# Sheet1.net
KiCad netlist of a schematic drawn in Altium Designer
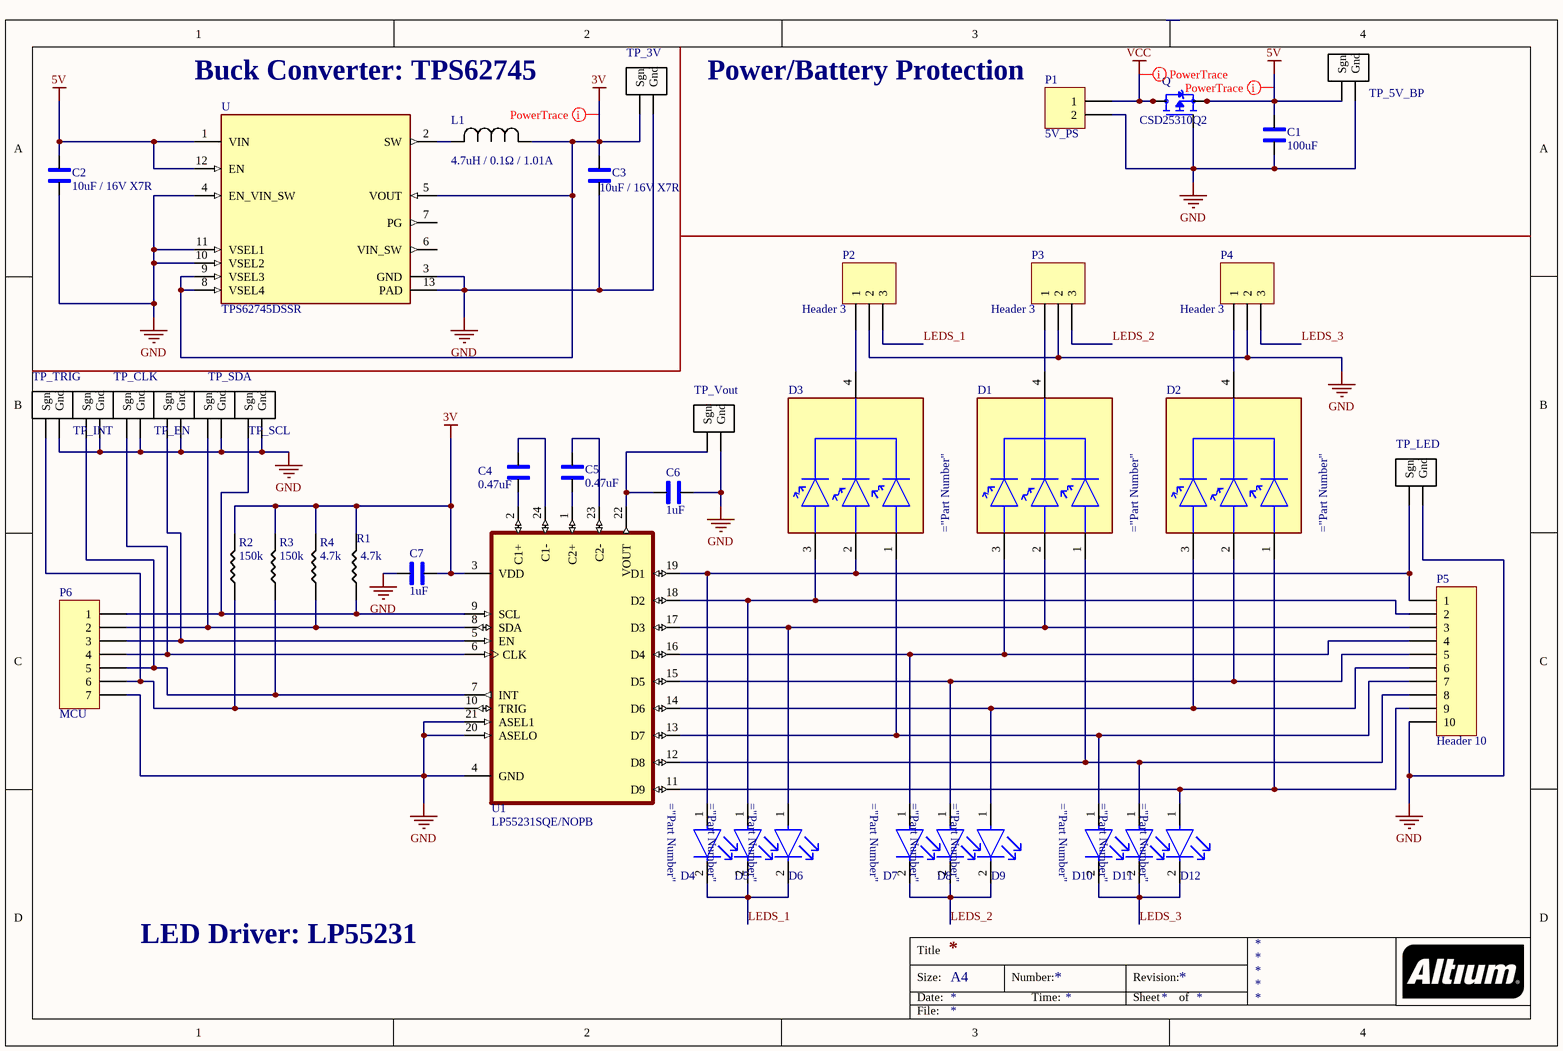
[diagram p0: Sheet1.SchDoc]

(export (version "E")
  (design (tool "Eeschema 10.0.6"))
  (components
    (comp (ref "C1")
      (value "100uF")
      (footprint "1206_Passive")
      (description "100µF X5R 1206 (3216 Metric)")
      (fields (field (name "DIGIKEY PART") "399-8150-1-ND") (field (name "MFR PART #") "CL31B105KBHNNNE"))
      (libsource (lib "ECEN5730Lib_2020_09_AR") (part "C_1uF_1206"))
    )
    (comp (ref "C2")
      (value "10uF / 16V X7R")
      (footprint "1206_Passive")
      (description "10µF ±20% 16V Ceramic Capacitor X7R 1206 (3216 Metric)")
      (fields (field (name "DIGIKEY PART") "399-8150-1-ND") (field (name "MFR PART #") "CL31B105KBHNNNE"))
      (libsource (lib "ECEN5730Lib_2020_09_AR") (part "C_1uF_1206"))
    )
    (comp (ref "C3")
      (value "10uF / 16V X7R")
      (footprint "1206_Passive")
      (description "10µF ±20% 16V Ceramic Capacitor X7R 1206 (3216 Metric)")
      (fields (field (name "DIGIKEY PART") "399-8150-1-ND") (field (name "MFR PART #") "CL31B105KBHNNNE"))
      (libsource (lib "ECEN5730Lib_2020_09_AR") (part "C_1uF_1206"))
    )
    (comp (ref "C4")
      (value "0.47uF")
      (footprint "1206_Passive")
      (description "0.47µF ±20% 16V Ceramic Capacitor X7R 1206 (3216 Metric)")
      (fields (field (name "DIGIKEY PART") "399-8150-1-ND") (field (name "MFR PART #") "CL31B105KBHNNNE"))
      (libsource (lib "ECEN5730Lib_2020_09_AR") (part "C_1uF_1206"))
    )
    (comp (ref "C5")
      (value "0.47uF")
      (footprint "1206_Passive")
      (description "0.47µF ±20% 16V Ceramic Capacitor X7R 1206 (3216 Metric)")
      (fields (field (name "DIGIKEY PART") "399-8150-1-ND") (field (name "MFR PART #") "CL31B105KBHNNNE"))
      (libsource (lib "ECEN5730Lib_2020_09_AR") (part "C_1uF_1206"))
    )
    (comp (ref "C6")
      (value "1uF")
      (footprint "1206_Passive")
      (description "1µF ±20% 16V Ceramic Capacitor X7R 1206 (3216 Metric)")
      (fields (field (name "DIGIKEY PART") "399-8150-1-ND") (field (name "MFR PART #") "CL31B105KBHNNNE"))
      (libsource (lib "ECEN5730Lib_2020_09_AR") (part "C_1uF_1206"))
    )
    (comp (ref "C7")
      (value "1uF")
      (footprint "1206_Passive")
      (description "1µF ±20% 16V Ceramic Capacitor X7R 1206 (3216 Metric)")
      (fields (field (name "DIGIKEY PART") "399-8150-1-ND") (field (name "MFR PART #") "CL31B105KBHNNNE"))
      (libsource (lib "ECEN5730Lib_2020_09_AR") (part "C_1uF_1206"))
    )
    (comp (ref "D1")
      (value "XZM2CRKM2DGFBB45SCCB")
      (footprint "SunLED_XZM2CRKM2DGFBB45SCCB_0")
      (libsource (lib "Schlib1") (part "XZM2CRKM2DGFBB45SCCB"))
    )
    (comp (ref "D2")
      (value "XZM2CRKM2DGFBB45SCCB")
      (footprint "SunLED_XZM2CRKM2DGFBB45SCCB_0")
      (libsource (lib "Schlib1") (part "XZM2CRKM2DGFBB45SCCB"))
    )
    (comp (ref "D3")
      (value "XZM2CRKM2DGFBB45SCCB")
      (footprint "SunLED_XZM2CRKM2DGFBB45SCCB_0")
      (libsource (lib "Schlib1") (part "XZM2CRKM2DGFBB45SCCB"))
    )
    (comp (ref "D4")
      (value "CLM3C-WKW-CWBYA453")
      (footprint "Cree_CLM3C-WKW_MFG")
      (libsource (lib "Schlib1") (part "CLM3C-WKW-CWBYA453"))
    )
    (comp (ref "D5")
      (value "CLM3C-WKW-CWBYA453")
      (footprint "Cree_CLM3C-WKW_MFG")
      (libsource (lib "Schlib1") (part "CLM3C-WKW-CWBYA453"))
    )
    (comp (ref "D6")
      (value "CLM3C-WKW-CWBYA453")
      (footprint "Cree_CLM3C-WKW_MFG")
      (libsource (lib "Schlib1") (part "CLM3C-WKW-CWBYA453"))
    )
    (comp (ref "D7")
      (value "CLM3C-WKW-CWBYA453")
      (footprint "Cree_CLM3C-WKW_MFG")
      (libsource (lib "Schlib1") (part "CLM3C-WKW-CWBYA453"))
    )
    (comp (ref "D8")
      (value "CLM3C-WKW-CWBYA453")
      (footprint "Cree_CLM3C-WKW_MFG")
      (libsource (lib "Schlib1") (part "CLM3C-WKW-CWBYA453"))
    )
    (comp (ref "D9")
      (value "CLM3C-WKW-CWBYA453")
      (footprint "Cree_CLM3C-WKW_MFG")
      (libsource (lib "Schlib1") (part "CLM3C-WKW-CWBYA453"))
    )
    (comp (ref "D10")
      (value "CLM3C-WKW-CWBYA453")
      (footprint "Cree_CLM3C-WKW_MFG")
      (libsource (lib "Schlib1") (part "CLM3C-WKW-CWBYA453"))
    )
    (comp (ref "D11")
      (value "CLM3C-WKW-CWBYA453")
      (footprint "Cree_CLM3C-WKW_MFG")
      (libsource (lib "Schlib1") (part "CLM3C-WKW-CWBYA453"))
    )
    (comp (ref "D12")
      (value "CLM3C-WKW-CWBYA453")
      (footprint "Cree_CLM3C-WKW_MFG")
      (libsource (lib "Schlib1") (part "CLM3C-WKW-CWBYA453"))
    )
    (comp (ref "L1")
      (value "4.7uH / 0.1Ω / 1.01A")
      (footprint "IND_IHLP-3232DZ")
      (description "4.7uH\r\n0.1Ω\r\n1.01A")
      (fields
        (field (name "MANUFACTURER_PART_NUMBER") "IHLP3232DZER5R6M11")
        (field (name "COPYRIGHT") "Copyright (C) 2018 Accelerated Designs. All rights reserved")
      )
      (libsource (lib "ECEN5730Lib_2020_09_AR") (part "L_5.6uH"))
    )
    (comp (ref "P1")
      (value "5V_PS")
      (footprint "HDR1X2")
      (description "Header, 2-Pin")
      (fields (field (name "PUBLISHER") "Altium Limited"))
      (libsource (lib "Miscellaneous Connectors") (part "Header 2"))
    )
    (comp (ref "P2")
      (value "Header 3")
      (footprint "HDR1X3")
      (description "Header, 3-Pin")
      (fields (field (name "PUBLISHER") "Altium Limited"))
      (libsource (lib "Miscellaneous Connectors") (part "Header 3"))
    )
    (comp (ref "P3")
      (value "Header 3")
      (footprint "HDR1X3")
      (description "Header, 3-Pin")
      (fields (field (name "PUBLISHER") "Altium Limited"))
      (libsource (lib "Miscellaneous Connectors") (part "Header 3"))
    )
    (comp (ref "P4")
      (value "Header 3")
      (footprint "HDR1X3")
      (description "Header, 3-Pin")
      (fields (field (name "PUBLISHER") "Altium Limited"))
      (libsource (lib "Miscellaneous Connectors") (part "Header 3"))
    )
    (comp (ref "P5")
      (value "Header 10")
      (footprint "HDR1X10")
      (description "Header, 10-Pin")
      (fields (field (name "PUBLISHER") "Altium Limited"))
      (libsource (lib "Miscellaneous Connectors") (part "Header 10"))
    )
    (comp (ref "P6")
      (value "MCU")
      (footprint "HDR1X7")
      (description "Header, 7-Pin")
      (fields (field (name "PUBLISHER") "Altium Limited"))
      (libsource (lib "Miscellaneous Connectors") (part "Header 7"))
    )
    (comp (ref "Q")
      (value "CSD25310Q2")
      (footprint "PcbLib1:TRANS_CSD25310Q2")
      (description "P-Channel 20V 20A _Ta_ 2.9W _Ta_ Surface Mount 6-WSON _2x2_")
      (fields (field (name "MF") "Texas Instruments"))
      (libsource (lib "Schlib1") (part "CSD25310Q2"))
    )
    (comp (ref "R1")
      (value "4.7k")
      (footprint "1206_Passive")
      (fields (field (name "DIGIKEY PART") "RNCP1206FTD1K00CT-ND") (field (name "Comment") "100m"))
      (libsource (lib "ECEN5730Lib_2020_09_AR") (part "R_100m_1206"))
    )
    (comp (ref "R2")
      (value "150k")
      (footprint "1206_Passive")
      (fields (field (name "DIGIKEY PART") "RNCP1206FTD1K00CT-ND") (field (name "Comment") "100m"))
      (libsource (lib "ECEN5730Lib_2020_09_AR") (part "R_100m_1206"))
    )
    (comp (ref "R3")
      (value "150k")
      (footprint "1206_Passive")
      (fields (field (name "DIGIKEY PART") "RNCP1206FTD1K00CT-ND") (field (name "Comment") "100m"))
      (libsource (lib "ECEN5730Lib_2020_09_AR") (part "R_100m_1206"))
    )
    (comp (ref "R4")
      (value "4.7k")
      (footprint "1206_Passive")
      (fields (field (name "DIGIKEY PART") "RNCP1206FTD1K00CT-ND") (field (name "Comment") "100m"))
      (libsource (lib "ECEN5730Lib_2020_09_AR") (part "R_100m_1206"))
    )
    (comp (ref "TP_3V")
      (value "10x Probe TP")
      (footprint "TP10x_Probe")
      (description "Test Point 300 mil centers")
      (libsource (lib "ECEN5730Lib_2020_09_AR") (part "TP_10x_Probe"))
    )
    (comp (ref "TP_5V_BP")
      (value "10x Probe TP")
      (footprint "TP10x_Probe")
      (description "Test Point 300 mil centers")
      (libsource (lib "ECEN5730Lib_2020_09_AR") (part "TP_10x_Probe"))
    )
    (comp (ref "TP_CLK")
      (value "10x Probe TP")
      (footprint "TP10x_Probe")
      (description "Test Point 300 mil centers")
      (libsource (lib "ECEN5730Lib_2020_09_AR") (part "TP_10x_Probe"))
    )
    (comp (ref "TP_EN")
      (value "10x Probe TP")
      (footprint "TP10x_Probe")
      (description "Test Point 300 mil centers")
      (libsource (lib "ECEN5730Lib_2020_09_AR") (part "TP_10x_Probe"))
    )
    (comp (ref "TP_INT")
      (value "10x Probe TP")
      (footprint "TP10x_Probe")
      (description "Test Point 300 mil centers")
      (libsource (lib "ECEN5730Lib_2020_09_AR") (part "TP_10x_Probe"))
    )
    (comp (ref "TP_LED")
      (value "10x Probe TP")
      (footprint "TP10x_Probe")
      (description "Test Point 300 mil centers")
      (libsource (lib "ECEN5730Lib_2020_09_AR") (part "TP_10x_Probe"))
    )
    (comp (ref "TP_SCL")
      (value "10x Probe TP")
      (footprint "TP10x_Probe")
      (description "Test Point 300 mil centers")
      (libsource (lib "ECEN5730Lib_2020_09_AR") (part "TP_10x_Probe"))
    )
    (comp (ref "TP_SDA")
      (value "10x Probe TP")
      (footprint "TP10x_Probe")
      (description "Test Point 300 mil centers")
      (libsource (lib "ECEN5730Lib_2020_09_AR") (part "TP_10x_Probe"))
    )
    (comp (ref "TP_TRIG")
      (value "10x Probe TP")
      (footprint "TP10x_Probe")
      (description "Test Point 300 mil centers")
      (libsource (lib "ECEN5730Lib_2020_09_AR") (part "TP_10x_Probe"))
    )
    (comp (ref "TP_Vout")
      (value "10x Probe TP")
      (footprint "TP10x_Probe")
      (description "Test Point 300 mil centers")
      (libsource (lib "ECEN5730Lib_2020_09_AR") (part "TP_10x_Probe"))
    )
    (comp (ref "U")
      (value "TPS62745DSSR")
      (footprint "PcbLib1:DSS0012A")
      (fields (field (name "MF") "Texas Instruments"))
      (libsource (lib "Schlib1") (part "TPS62745DSSR"))
    )
    (comp (ref "U1")
      (value "LP55231SQE/NOPB")
      (footprint "QFN50P400X400X80-25N")
      (fields (field (name "MF") "Texas Instruments"))
      (libsource (lib "Schlib1") (part "LP55231SQE/NOPB"))
    )
  )
  (nets
    (net (code "1") (name "/LEDS_1") (class "Default")
      (node (ref "D4") (pin "2") (pinfunction "C_2") (pintype "passive"))
      (node (ref "D5") (pin "2") (pinfunction "C_2") (pintype "passive"))
      (node (ref "D6") (pin "2") (pinfunction "C_2") (pintype "passive"))
      (node (ref "P2") (pin "3") (pinfunction "3_3") (pintype "passive"))
    )
    (net (code "2") (name "/LEDS_2") (class "Default")
      (node (ref "D7") (pin "2") (pinfunction "C_2") (pintype "passive"))
      (node (ref "D8") (pin "2") (pinfunction "C_2") (pintype "passive"))
      (node (ref "D9") (pin "2") (pinfunction "C_2") (pintype "passive"))
      (node (ref "P3") (pin "3") (pinfunction "3_3") (pintype "passive"))
    )
    (net (code "3") (name "/LEDS_3") (class "Default")
      (node (ref "D10") (pin "2") (pinfunction "C_2") (pintype "passive"))
      (node (ref "D11") (pin "2") (pinfunction "C_2") (pintype "passive"))
      (node (ref "D12") (pin "2") (pinfunction "C_2") (pintype "passive"))
      (node (ref "P4") (pin "3") (pinfunction "3_3") (pintype "passive"))
    )
    (net (code "4") (name "3V") (class "Default")
      (node (ref "C3") (pin "2") (pinfunction "2_2") (pintype "passive"))
      (node (ref "C7") (pin "1") (pinfunction "1_1") (pintype "passive"))
      (node (ref "L1") (pin "1") (pinfunction "1_1") (pintype "passive"))
      (node (ref "R1") (pin "2") (pinfunction "2_2") (pintype "passive"))
      (node (ref "R2") (pin "2") (pinfunction "2_2") (pintype "passive"))
      (node (ref "R3") (pin "2") (pinfunction "2_2") (pintype "passive"))
      (node (ref "R4") (pin "2") (pinfunction "2_2") (pintype "passive"))
      (node (ref "TP_3V") (pin "1") (pinfunction "Sgn_1") (pintype "passive"))
      (node (ref "U") (pin "5") (pinfunction "VOUT_5") (pintype "input"))
      (node (ref "U") (pin "8") (pinfunction "VSEL4_8") (pintype "input"))
      (node (ref "U") (pin "9") (pinfunction "VSEL3_9") (pintype "input"))
      (node (ref "U1") (pin "3") (pinfunction "VDD_3") (pintype "power_in"))
    )
    (net (code "5") (name "5V") (class "Default")
      (node (ref "C1") (pin "2") (pinfunction "2_2") (pintype "passive"))
      (node (ref "C2") (pin "2") (pinfunction "2_2") (pintype "passive"))
      (node (ref "Q") (pin "1") (pinfunction "S_1") (pintype "passive"))
      (node (ref "Q") (pin "2") (pinfunction "S_2") (pintype "passive"))
      (node (ref "Q") (pin "5") (pinfunction "S_5") (pintype "passive"))
      (node (ref "Q") (pin "6") (pinfunction "S_6") (pintype "passive"))
      (node (ref "Q") (pin "7") (pinfunction "S_7") (pintype "passive"))
      (node (ref "TP_5V_BP") (pin "1") (pinfunction "Sgn_1") (pintype "passive"))
      (node (ref "U") (pin "1") (pinfunction "VIN_1") (pintype "power_in"))
      (node (ref "U") (pin "12") (pinfunction "EN_12") (pintype "input"))
    )
    (net (code "6") (name "GND") (class "Default")
      (node (ref "C1") (pin "1") (pinfunction "1_1") (pintype "passive"))
      (node (ref "C2") (pin "1") (pinfunction "1_1") (pintype "passive"))
      (node (ref "C3") (pin "1") (pinfunction "1_1") (pintype "passive"))
      (node (ref "C6") (pin "2") (pinfunction "2_2") (pintype "passive"))
      (node (ref "C7") (pin "2") (pinfunction "2_2") (pintype "passive"))
      (node (ref "P1") (pin "2") (pinfunction "2_2") (pintype "passive"))
      (node (ref "P2") (pin "2") (pinfunction "2_2") (pintype "passive"))
      (node (ref "P3") (pin "2") (pinfunction "2_2") (pintype "passive"))
      (node (ref "P4") (pin "2") (pinfunction "2_2") (pintype "passive"))
      (node (ref "P5") (pin "10") (pinfunction "10_10") (pintype "passive"))
      (node (ref "P6") (pin "7") (pinfunction "7_7") (pintype "passive"))
      (node (ref "Q") (pin "3") (pinfunction "G_3") (pintype "passive"))
      (node (ref "TP_3V") (pin "2") (pinfunction "Gnd_2") (pintype "passive"))
      (node (ref "TP_5V_BP") (pin "2") (pinfunction "Gnd_2") (pintype "passive"))
      (node (ref "TP_CLK") (pin "2") (pinfunction "Gnd_2") (pintype "passive"))
      (node (ref "TP_EN") (pin "2") (pinfunction "Gnd_2") (pintype "passive"))
      (node (ref "TP_INT") (pin "2") (pinfunction "Gnd_2") (pintype "passive"))
      (node (ref "TP_LED") (pin "2") (pinfunction "Gnd_2") (pintype "passive"))
      (node (ref "TP_SCL") (pin "2") (pinfunction "Gnd_2") (pintype "passive"))
      (node (ref "TP_SDA") (pin "2") (pinfunction "Gnd_2") (pintype "passive"))
      (node (ref "TP_TRIG") (pin "2") (pinfunction "Gnd_2") (pintype "passive"))
      (node (ref "TP_Vout") (pin "2") (pinfunction "Gnd_2") (pintype "passive"))
      (node (ref "U") (pin "10") (pinfunction "VSEL2_10") (pintype "input"))
      (node (ref "U") (pin "11") (pinfunction "VSEL1_11") (pintype "input"))
      (node (ref "U") (pin "13") (pinfunction "PAD_13") (pintype "passive"))
      (node (ref "U") (pin "3") (pinfunction "GND_3") (pintype "power_in"))
      (node (ref "U") (pin "4") (pinfunction "EN_VIN_SW_4") (pintype "input"))
      (node (ref "U1") (pin "20") (pinfunction "ASELO_20") (pintype "input"))
      (node (ref "U1") (pin "21") (pinfunction "ASEL1_21") (pintype "input"))
      (node (ref "U1") (pin "4") (pinfunction "GND_4") (pintype "power_in"))
    )
    (net (code "7") (name "Net-(D1-BLUE_A)") (class "Default")
      (node (ref "D1") (pin "3") (pinfunction "BLUE_A_3") (pintype "passive"))
      (node (ref "D7") (pin "1") (pinfunction "A_1") (pintype "passive"))
      (node (ref "P5") (pin "4") (pinfunction "4_4") (pintype "passive"))
      (node (ref "U1") (pin "16") (pinfunction "D4_16") (pintype "bidirectional"))
    )
    (net (code "8") (name "Net-(D1-COMMON_CATHODE)") (class "Default")
      (node (ref "D1") (pin "4") (pinfunction "COMMON_CATHODE_4") (pintype "passive"))
      (node (ref "P3") (pin "1") (pinfunction "1_1") (pintype "passive"))
    )
    (net (code "9") (name "Net-(D1-GREEN_A)") (class "Default")
      (node (ref "D1") (pin "2") (pinfunction "GREEN_A_2") (pintype "passive"))
      (node (ref "D6") (pin "1") (pinfunction "A_1") (pintype "passive"))
      (node (ref "P5") (pin "3") (pinfunction "3_3") (pintype "passive"))
      (node (ref "U1") (pin "17") (pinfunction "D3_17") (pintype "bidirectional"))
    )
    (net (code "10") (name "Net-(D1-RED_A)") (class "Default")
      (node (ref "D1") (pin "1") (pinfunction "RED_A_1") (pintype "passive"))
      (node (ref "D11") (pin "1") (pinfunction "A_1") (pintype "passive"))
      (node (ref "P5") (pin "8") (pinfunction "8_8") (pintype "passive"))
      (node (ref "U1") (pin "12") (pinfunction "D8_12") (pintype "bidirectional"))
    )
    (net (code "11") (name "Net-(D2-BLUE_A)") (class "Default")
      (node (ref "D2") (pin "3") (pinfunction "BLUE_A_3") (pintype "passive"))
      (node (ref "D9") (pin "1") (pinfunction "A_1") (pintype "passive"))
      (node (ref "P5") (pin "6") (pinfunction "6_6") (pintype "passive"))
      (node (ref "U1") (pin "14") (pinfunction "D6_14") (pintype "bidirectional"))
    )
    (net (code "12") (name "Net-(D2-COMMON_CATHODE)") (class "Default")
      (node (ref "D2") (pin "4") (pinfunction "COMMON_CATHODE_4") (pintype "passive"))
      (node (ref "P4") (pin "1") (pinfunction "1_1") (pintype "passive"))
    )
    (net (code "13") (name "Net-(D2-GREEN_A)") (class "Default")
      (node (ref "D2") (pin "2") (pinfunction "GREEN_A_2") (pintype "passive"))
      (node (ref "D8") (pin "1") (pinfunction "A_1") (pintype "passive"))
      (node (ref "P5") (pin "5") (pinfunction "5_5") (pintype "passive"))
      (node (ref "U1") (pin "15") (pinfunction "D5_15") (pintype "bidirectional"))
    )
    (net (code "14") (name "Net-(D3-BLUE_A)") (class "Default")
      (node (ref "D3") (pin "3") (pinfunction "BLUE_A_3") (pintype "passive"))
      (node (ref "D5") (pin "1") (pinfunction "A_1") (pintype "passive"))
      (node (ref "P5") (pin "2") (pinfunction "2_2") (pintype "passive"))
      (node (ref "U1") (pin "18") (pinfunction "D2_18") (pintype "bidirectional"))
    )
    (net (code "15") (name "Net-(D3-COMMON_CATHODE)") (class "Default")
      (node (ref "D3") (pin "4") (pinfunction "COMMON_CATHODE_4") (pintype "passive"))
      (node (ref "P2") (pin "1") (pinfunction "1_1") (pintype "passive"))
    )
    (net (code "16") (name "Net-(D3-GREEN_A)") (class "Default")
      (node (ref "D3") (pin "2") (pinfunction "GREEN_A_2") (pintype "passive"))
      (node (ref "D4") (pin "1") (pinfunction "A_1") (pintype "passive"))
      (node (ref "P5") (pin "1") (pinfunction "1_1") (pintype "passive"))
      (node (ref "TP_LED") (pin "1") (pinfunction "Sgn_1") (pintype "passive"))
      (node (ref "U1") (pin "19") (pinfunction "D1_19") (pintype "bidirectional"))
    )
    (net (code "17") (name "Net-(D10-A)") (class "Default")
      (node (ref "D10") (pin "1") (pinfunction "A_1") (pintype "passive"))
      (node (ref "D3") (pin "1") (pinfunction "RED_A_1") (pintype "passive"))
      (node (ref "P5") (pin "7") (pinfunction "7_7") (pintype "passive"))
      (node (ref "U1") (pin "13") (pinfunction "D7_13") (pintype "bidirectional"))
    )
    (net (code "18") (name "Net-(D12-A)") (class "Default")
      (node (ref "D12") (pin "1") (pinfunction "A_1") (pintype "passive"))
      (node (ref "D2") (pin "1") (pinfunction "RED_A_1") (pintype "passive"))
      (node (ref "P5") (pin "9") (pinfunction "9_9") (pintype "passive"))
      (node (ref "U1") (pin "11") (pinfunction "D9_11") (pintype "bidirectional"))
    )
    (net (code "19") (name "Net-(TP_CLK-Sgn)") (class "Default")
      (node (ref "P6") (pin "4") (pinfunction "4_4") (pintype "passive"))
      (node (ref "TP_CLK") (pin "1") (pinfunction "Sgn_1") (pintype "passive"))
      (node (ref "U1") (pin "6") (pinfunction "CLK_6") (pintype "input"))
    )
    (net (code "20") (name "Net-(TP_EN-Sgn)") (class "Default")
      (node (ref "P6") (pin "3") (pinfunction "3_3") (pintype "passive"))
      (node (ref "TP_EN") (pin "1") (pinfunction "Sgn_1") (pintype "passive"))
      (node (ref "U1") (pin "5") (pinfunction "EN_5") (pintype "input"))
    )
    (net (code "21") (name "Net-(TP_INT-Sgn)") (class "Default")
      (node (ref "P6") (pin "5") (pinfunction "5_5") (pintype "passive"))
      (node (ref "R3") (pin "1") (pinfunction "1_1") (pintype "passive"))
      (node (ref "TP_INT") (pin "1") (pinfunction "Sgn_1") (pintype "passive"))
      (node (ref "U1") (pin "7") (pinfunction "INT_7") (pintype "output"))
    )
    (net (code "22") (name "Net-(TP_SCL-Sgn)") (class "Default")
      (node (ref "P6") (pin "1") (pinfunction "1_1") (pintype "passive"))
      (node (ref "R1") (pin "1") (pinfunction "1_1") (pintype "passive"))
      (node (ref "TP_SCL") (pin "1") (pinfunction "Sgn_1") (pintype "passive"))
      (node (ref "U1") (pin "9") (pinfunction "SCL_9") (pintype "input"))
    )
    (net (code "23") (name "Net-(TP_SDA-Sgn)") (class "Default")
      (node (ref "P6") (pin "2") (pinfunction "2_2") (pintype "passive"))
      (node (ref "R4") (pin "1") (pinfunction "1_1") (pintype "passive"))
      (node (ref "TP_SDA") (pin "1") (pinfunction "Sgn_1") (pintype "passive"))
      (node (ref "U1") (pin "8") (pinfunction "SDA_8") (pintype "bidirectional"))
    )
    (net (code "24") (name "Net-(TP_TRIG-Sgn)") (class "Default")
      (node (ref "P6") (pin "6") (pinfunction "6_6") (pintype "passive"))
      (node (ref "R2") (pin "1") (pinfunction "1_1") (pintype "passive"))
      (node (ref "TP_TRIG") (pin "1") (pinfunction "Sgn_1") (pintype "passive"))
      (node (ref "U1") (pin "10") (pinfunction "TRIG_10") (pintype "bidirectional"))
    )
    (net (code "25") (name "Net-(TP_Vout-Sgn)") (class "Default")
      (node (ref "C6") (pin "1") (pinfunction "1_1") (pintype "passive"))
      (node (ref "TP_Vout") (pin "1") (pinfunction "Sgn_1") (pintype "passive"))
      (node (ref "U1") (pin "22") (pinfunction "VOUT_22") (pintype "output"))
    )
    (net (code "26") (name "Net-(U-SW)") (class "Default")
      (node (ref "L1") (pin "2") (pinfunction "2_2") (pintype "passive"))
      (node (ref "U") (pin "2") (pinfunction "SW_2") (pintype "output"))
    )
    (net (code "27") (name "Net-(U1-C1+)") (class "Default")
      (node (ref "C4") (pin "1") (pinfunction "1_1") (pintype "passive"))
      (node (ref "U1") (pin "2") (pinfunction "C1+_2") (pintype "bidirectional"))
    )
    (net (code "28") (name "Net-(U1-C1-)") (class "Default")
      (node (ref "C4") (pin "2") (pinfunction "2_2") (pintype "passive"))
      (node (ref "U1") (pin "24") (pinfunction "C1-_24") (pintype "bidirectional"))
    )
    (net (code "29") (name "Net-(U1-C2+)") (class "Default")
      (node (ref "C5") (pin "1") (pinfunction "1_1") (pintype "passive"))
      (node (ref "U1") (pin "1") (pinfunction "C2+_1") (pintype "bidirectional"))
    )
    (net (code "30") (name "Net-(U1-C2-)") (class "Default")
      (node (ref "C5") (pin "2") (pinfunction "2_2") (pintype "passive"))
      (node (ref "U1") (pin "23") (pinfunction "C2-_23") (pintype "bidirectional"))
    )
    (net (code "31") (name "VCC") (class "Default")
      (node (ref "P1") (pin "1") (pinfunction "1_1") (pintype "passive"))
      (node (ref "Q") (pin "4") (pinfunction "D_4") (pintype "passive"))
      (node (ref "Q") (pin "8") (pinfunction "D_8") (pintype "passive"))
    )
    (net (code "32") (name "unconnected-(U-PG-Pad7)") (class "Default")
      (node (ref "U") (pin "7") (pinfunction "PG_7") (pintype "output"))
    )
    (net (code "33") (name "unconnected-(U-VIN_SW-Pad6)") (class "Default")
      (node (ref "U") (pin "6") (pinfunction "VIN_SW_6") (pintype "output"))
    )
  )
)
